# 328pb_squinch_v1.net
KiCad netlist of a schematic drawn in EAGLE
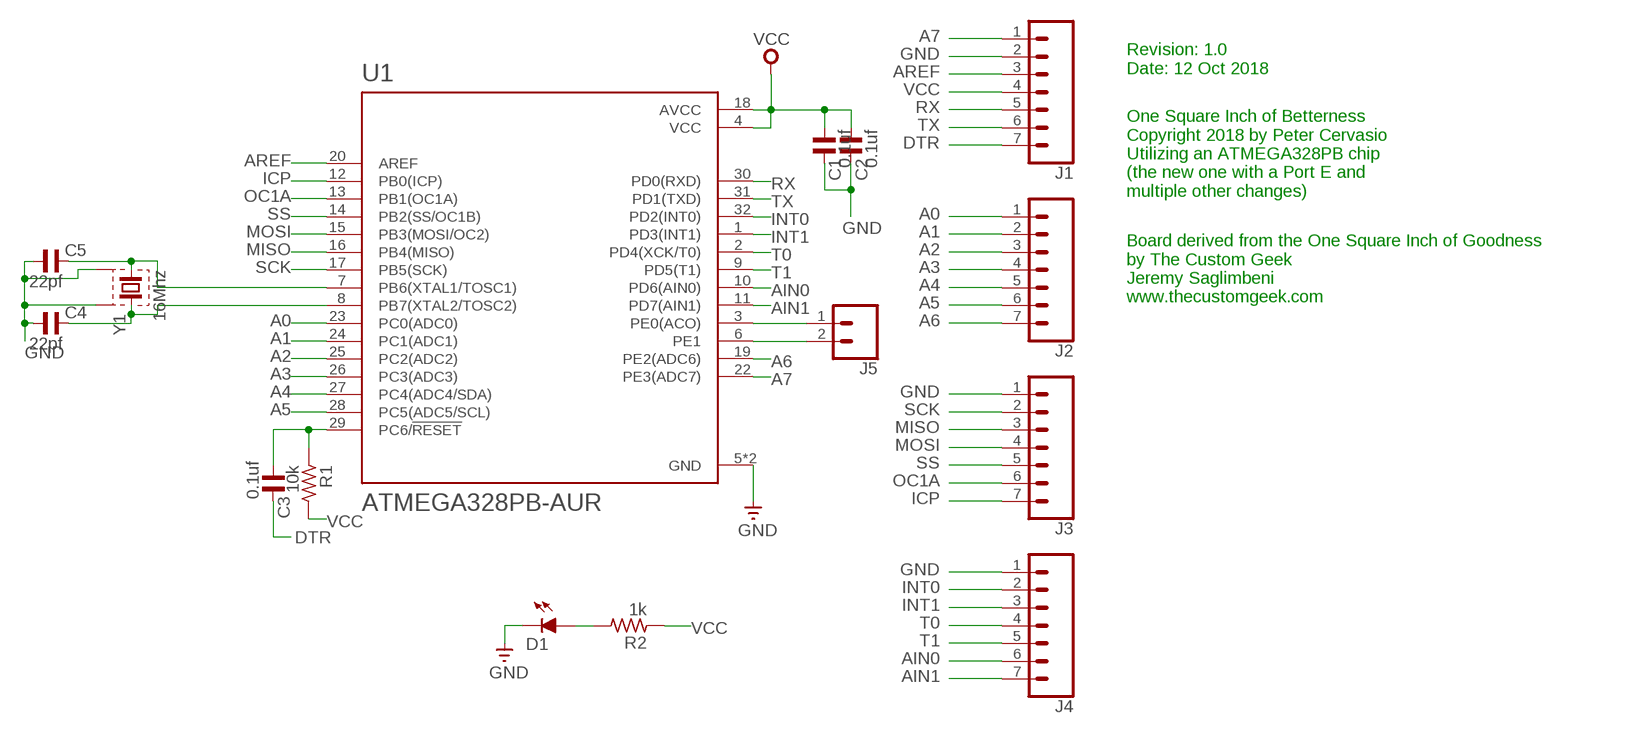
[diagram p0: schematic, sheet 1]

(export (version "E")
  (design (tool "Eeschema 10.0.6"))
  (components
    (comp (ref "C1")
      (value "0.1uf")
      (footprint "eagle-import:C0603")
      (libsource (lib "eagle-import") (part "C_0603"))
    )
    (comp (ref "C2")
      (value "0.1uf")
      (footprint "eagle-import:C0603")
      (libsource (lib "eagle-import") (part "C_0603"))
    )
    (comp (ref "C3")
      (value "0.1uf")
      (footprint "eagle-import:C0603")
      (libsource (lib "eagle-import") (part "C_0603"))
    )
    (comp (ref "C4")
      (value "22pf")
      (footprint "eagle-import:C0603")
      (libsource (lib "eagle-import") (part "C_0603"))
    )
    (comp (ref "C5")
      (value "22pf")
      (footprint "eagle-import:C0603")
      (libsource (lib "eagle-import") (part "C_0603"))
    )
    (comp (ref "D1")
      (value "LEDCHIPLED_0603")
      (footprint "eagle-import:CHIPLED_0603")
      (libsource (lib "eagle-import") (part "LEDCHIPLED_0603"))
    )
    (comp (ref "J1")
      (value "CONN_07")
      (footprint "eagle-import:1X07")
      (libsource (lib "eagle-import") (part "CONN_07"))
    )
    (comp (ref "J2")
      (value "CONN_07")
      (footprint "eagle-import:1X07")
      (libsource (lib "eagle-import") (part "CONN_07"))
    )
    (comp (ref "J3")
      (value "CONN_07")
      (footprint "eagle-import:1X07")
      (libsource (lib "eagle-import") (part "CONN_07"))
    )
    (comp (ref "J4")
      (value "CONN_07")
      (footprint "eagle-import:1X07")
      (libsource (lib "eagle-import") (part "CONN_07"))
    )
    (comp (ref "J5")
      (value "CONN_02")
      (footprint "eagle-import:1X02")
      (libsource (lib "eagle-import") (part "CONN_02"))
    )
    (comp (ref "R1")
      (value "10k")
      (footprint "eagle-import:R0603")
      (libsource (lib "eagle-import") (part "R_0603"))
    )
    (comp (ref "R2")
      (value "1k")
      (footprint "eagle-import:R0603")
      (libsource (lib "eagle-import") (part "R_0603"))
    )
    (comp (ref "U1")
      (value "ATMEGA328PB-AUR")
      (footprint "eagle-import:QFP80P900X900X120-32N")
      (fields (field (name "MF") "Microchip"))
      (libsource (lib "eagle-import") (part "ATMEGA328PB-AUR"))
    )
    (comp (ref "Y1")
      (value "16Mhz")
      (footprint "eagle-import:ABM3B")
      (libsource (lib "eagle-import") (part "ABM3B"))
    )
  )
  (nets
    (net (code "1") (name "/A0") (class "Default")
      (node (ref "J2") (pin "1") (pinfunction "1_1") (pintype "passive"))
      (node (ref "U1") (pin "23") (pinfunction "PC0(ADC0)_23") (pintype "bidirectional"))
    )
    (net (code "2") (name "/A1") (class "Default")
      (node (ref "J2") (pin "2") (pinfunction "2_2") (pintype "passive"))
      (node (ref "U1") (pin "24") (pinfunction "PC1(ADC1)_24") (pintype "bidirectional"))
    )
    (net (code "3") (name "/A2") (class "Default")
      (node (ref "J2") (pin "3") (pinfunction "3_3") (pintype "passive"))
      (node (ref "U1") (pin "25") (pinfunction "PC2(ADC2)_25") (pintype "bidirectional"))
    )
    (net (code "4") (name "/A3") (class "Default")
      (node (ref "J2") (pin "4") (pinfunction "4_4") (pintype "passive"))
      (node (ref "U1") (pin "26") (pinfunction "PC3(ADC3)_26") (pintype "bidirectional"))
    )
    (net (code "5") (name "/A4") (class "Default")
      (node (ref "J2") (pin "5") (pinfunction "5_5") (pintype "passive"))
      (node (ref "U1") (pin "27") (pinfunction "PC4(ADC4/SDA)_27") (pintype "bidirectional"))
    )
    (net (code "6") (name "/A5") (class "Default")
      (node (ref "J2") (pin "6") (pinfunction "6_6") (pintype "passive"))
      (node (ref "U1") (pin "28") (pinfunction "PC5(ADC5/SCL)_28") (pintype "bidirectional"))
    )
    (net (code "7") (name "/A6") (class "Default")
      (node (ref "J2") (pin "7") (pinfunction "7_7") (pintype "passive"))
      (node (ref "U1") (pin "19") (pinfunction "PE2(ADC6)_19") (pintype "bidirectional"))
    )
    (net (code "8") (name "/A7") (class "Default")
      (node (ref "J1") (pin "1") (pinfunction "1_1") (pintype "passive"))
      (node (ref "U1") (pin "22") (pinfunction "PE3(ADC7)_22") (pintype "bidirectional"))
    )
    (net (code "9") (name "/AIN0") (class "Default")
      (node (ref "J4") (pin "6") (pinfunction "6_6") (pintype "passive"))
      (node (ref "U1") (pin "10") (pinfunction "PD6(AIN0)_10") (pintype "bidirectional"))
    )
    (net (code "10") (name "/AIN1") (class "Default")
      (node (ref "J4") (pin "7") (pinfunction "7_7") (pintype "passive"))
      (node (ref "U1") (pin "11") (pinfunction "PD7(AIN1)_11") (pintype "bidirectional"))
    )
    (net (code "11") (name "/AREF") (class "Default")
      (node (ref "J1") (pin "3") (pinfunction "3_3") (pintype "passive"))
      (node (ref "U1") (pin "20") (pinfunction "AREF_20") (pintype "input"))
    )
    (net (code "12") (name "/DTR") (class "Default")
      (node (ref "C3") (pin "2") (pinfunction "2_2") (pintype "passive"))
      (node (ref "J1") (pin "7") (pinfunction "7_7") (pintype "passive"))
    )
    (net (code "13") (name "/ICP") (class "Default")
      (node (ref "J3") (pin "7") (pinfunction "7_7") (pintype "passive"))
      (node (ref "U1") (pin "12") (pinfunction "PB0(ICP)_12") (pintype "bidirectional"))
    )
    (net (code "14") (name "/INT0") (class "Default")
      (node (ref "J4") (pin "2") (pinfunction "2_2") (pintype "passive"))
      (node (ref "U1") (pin "32") (pinfunction "PD2(INT0)_32") (pintype "bidirectional"))
    )
    (net (code "15") (name "/INT1") (class "Default")
      (node (ref "J4") (pin "3") (pinfunction "3_3") (pintype "passive"))
      (node (ref "U1") (pin "1") (pinfunction "PD3(INT1)_1") (pintype "bidirectional"))
    )
    (net (code "16") (name "/MISO") (class "Default")
      (node (ref "J3") (pin "3") (pinfunction "3_3") (pintype "passive"))
      (node (ref "U1") (pin "16") (pinfunction "PB4(MISO)_16") (pintype "bidirectional"))
    )
    (net (code "17") (name "/MOSI") (class "Default")
      (node (ref "J3") (pin "4") (pinfunction "4_4") (pintype "passive"))
      (node (ref "U1") (pin "15") (pinfunction "PB3(MOSI/OC2)_15") (pintype "bidirectional"))
    )
    (net (code "18") (name "/OC1A") (class "Default")
      (node (ref "J3") (pin "6") (pinfunction "6_6") (pintype "passive"))
      (node (ref "U1") (pin "13") (pinfunction "PB1(OC1A)_13") (pintype "bidirectional"))
    )
    (net (code "19") (name "/RX") (class "Default")
      (node (ref "J1") (pin "5") (pinfunction "5_5") (pintype "passive"))
      (node (ref "U1") (pin "30") (pinfunction "PD0(RXD)_30") (pintype "bidirectional"))
    )
    (net (code "20") (name "/SCK") (class "Default")
      (node (ref "J3") (pin "2") (pinfunction "2_2") (pintype "passive"))
      (node (ref "U1") (pin "17") (pinfunction "PB5(SCK)_17") (pintype "bidirectional"))
    )
    (net (code "21") (name "/SS") (class "Default")
      (node (ref "J3") (pin "5") (pinfunction "5_5") (pintype "passive"))
      (node (ref "U1") (pin "14") (pinfunction "PB2(SS/OC1B)_14") (pintype "bidirectional"))
    )
    (net (code "22") (name "/T0") (class "Default")
      (node (ref "J4") (pin "4") (pinfunction "4_4") (pintype "passive"))
      (node (ref "U1") (pin "2") (pinfunction "PD4(XCK/T0)_2") (pintype "bidirectional"))
    )
    (net (code "23") (name "/T1") (class "Default")
      (node (ref "J4") (pin "5") (pinfunction "5_5") (pintype "passive"))
      (node (ref "U1") (pin "9") (pinfunction "PD5(T1)_9") (pintype "bidirectional"))
    )
    (net (code "24") (name "/TX") (class "Default")
      (node (ref "J1") (pin "6") (pinfunction "6_6") (pintype "passive"))
      (node (ref "U1") (pin "31") (pinfunction "PD1(TXD)_31") (pintype "bidirectional"))
    )
    (net (code "25") (name "GND") (class "Default")
      (node (ref "C1") (pin "1") (pinfunction "1_1") (pintype "passive"))
      (node (ref "C2") (pin "1") (pinfunction "1_1") (pintype "passive"))
      (node (ref "C4") (pin "1") (pinfunction "1_1") (pintype "passive"))
      (node (ref "C5") (pin "1") (pinfunction "1_1") (pintype "passive"))
      (node (ref "D1") (pin "C") (pinfunction "C_C") (pintype "passive"))
      (node (ref "J1") (pin "2") (pinfunction "2_2") (pintype "passive"))
      (node (ref "J3") (pin "1") (pinfunction "1_1") (pintype "passive"))
      (node (ref "J4") (pin "1") (pinfunction "1_1") (pintype "passive"))
      (node (ref "U1") (pin "21") (pinfunction "GND_21") (pintype "power_in"))
      (node (ref "U1") (pin "5") (pinfunction "GND_5") (pintype "power_in"))
      (node (ref "Y1") (pin "2") (pinfunction "2_2") (pintype "passive"))
      (node (ref "Y1") (pin "4") (pinfunction "4_4") (pintype "passive"))
    )
    (net (code "26") (name "Net-(D1-PadA)") (class "Default")
      (node (ref "D1") (pin "A") (pinfunction "A_A") (pintype "passive"))
      (node (ref "R2") (pin "2") (pinfunction "2_2") (pintype "passive"))
    )
    (net (code "27") (name "Net-(U1-PB6(XTAL1{slash}TOSC1))") (class "Default")
      (node (ref "C5") (pin "2") (pinfunction "2_2") (pintype "passive"))
      (node (ref "U1") (pin "7") (pinfunction "PB6(XTAL1/TOSC1)_7") (pintype "bidirectional"))
      (node (ref "Y1") (pin "1") (pinfunction "1_1") (pintype "passive"))
    )
    (net (code "28") (name "Net-(U1-PB7(XTAL2{slash}TOSC2))") (class "Default")
      (node (ref "C4") (pin "2") (pinfunction "2_2") (pintype "passive"))
      (node (ref "U1") (pin "8") (pinfunction "PB7(XTAL2/TOSC2)_8") (pintype "bidirectional"))
      (node (ref "Y1") (pin "3") (pinfunction "3_3") (pintype "passive"))
    )
    (net (code "29") (name "Net-(U1-PC6{slash}~{RESET})") (class "Default")
      (node (ref "C3") (pin "1") (pinfunction "1_1") (pintype "passive"))
      (node (ref "R1") (pin "1") (pinfunction "1_1") (pintype "passive"))
      (node (ref "U1") (pin "29") (pinfunction "PC6/~{RESET}_29") (pintype "bidirectional"))
    )
    (net (code "30") (name "Net-(U1-PE0(ACO))") (class "Default")
      (node (ref "J5") (pin "1") (pinfunction "1_1") (pintype "passive"))
      (node (ref "U1") (pin "3") (pinfunction "PE0(ACO)_3") (pintype "bidirectional"))
    )
    (net (code "31") (name "Net-(U1-PE1)") (class "Default")
      (node (ref "J5") (pin "2") (pinfunction "2_2") (pintype "passive"))
      (node (ref "U1") (pin "6") (pinfunction "PE1_6") (pintype "bidirectional"))
    )
    (net (code "32") (name "VCC") (class "Default")
      (node (ref "C1") (pin "2") (pinfunction "2_2") (pintype "passive"))
      (node (ref "C2") (pin "2") (pinfunction "2_2") (pintype "passive"))
      (node (ref "J1") (pin "4") (pinfunction "4_4") (pintype "passive"))
      (node (ref "R1") (pin "2") (pinfunction "2_2") (pintype "passive"))
      (node (ref "R2") (pin "1") (pinfunction "1_1") (pintype "passive"))
      (node (ref "U1") (pin "18") (pinfunction "AVCC_18") (pintype "power_in"))
      (node (ref "U1") (pin "4") (pinfunction "VCC_4") (pintype "power_in"))
    )
  )
)
